# leo_joy_gamer.net
KiCad netlist of a schematic drawn in EAGLE
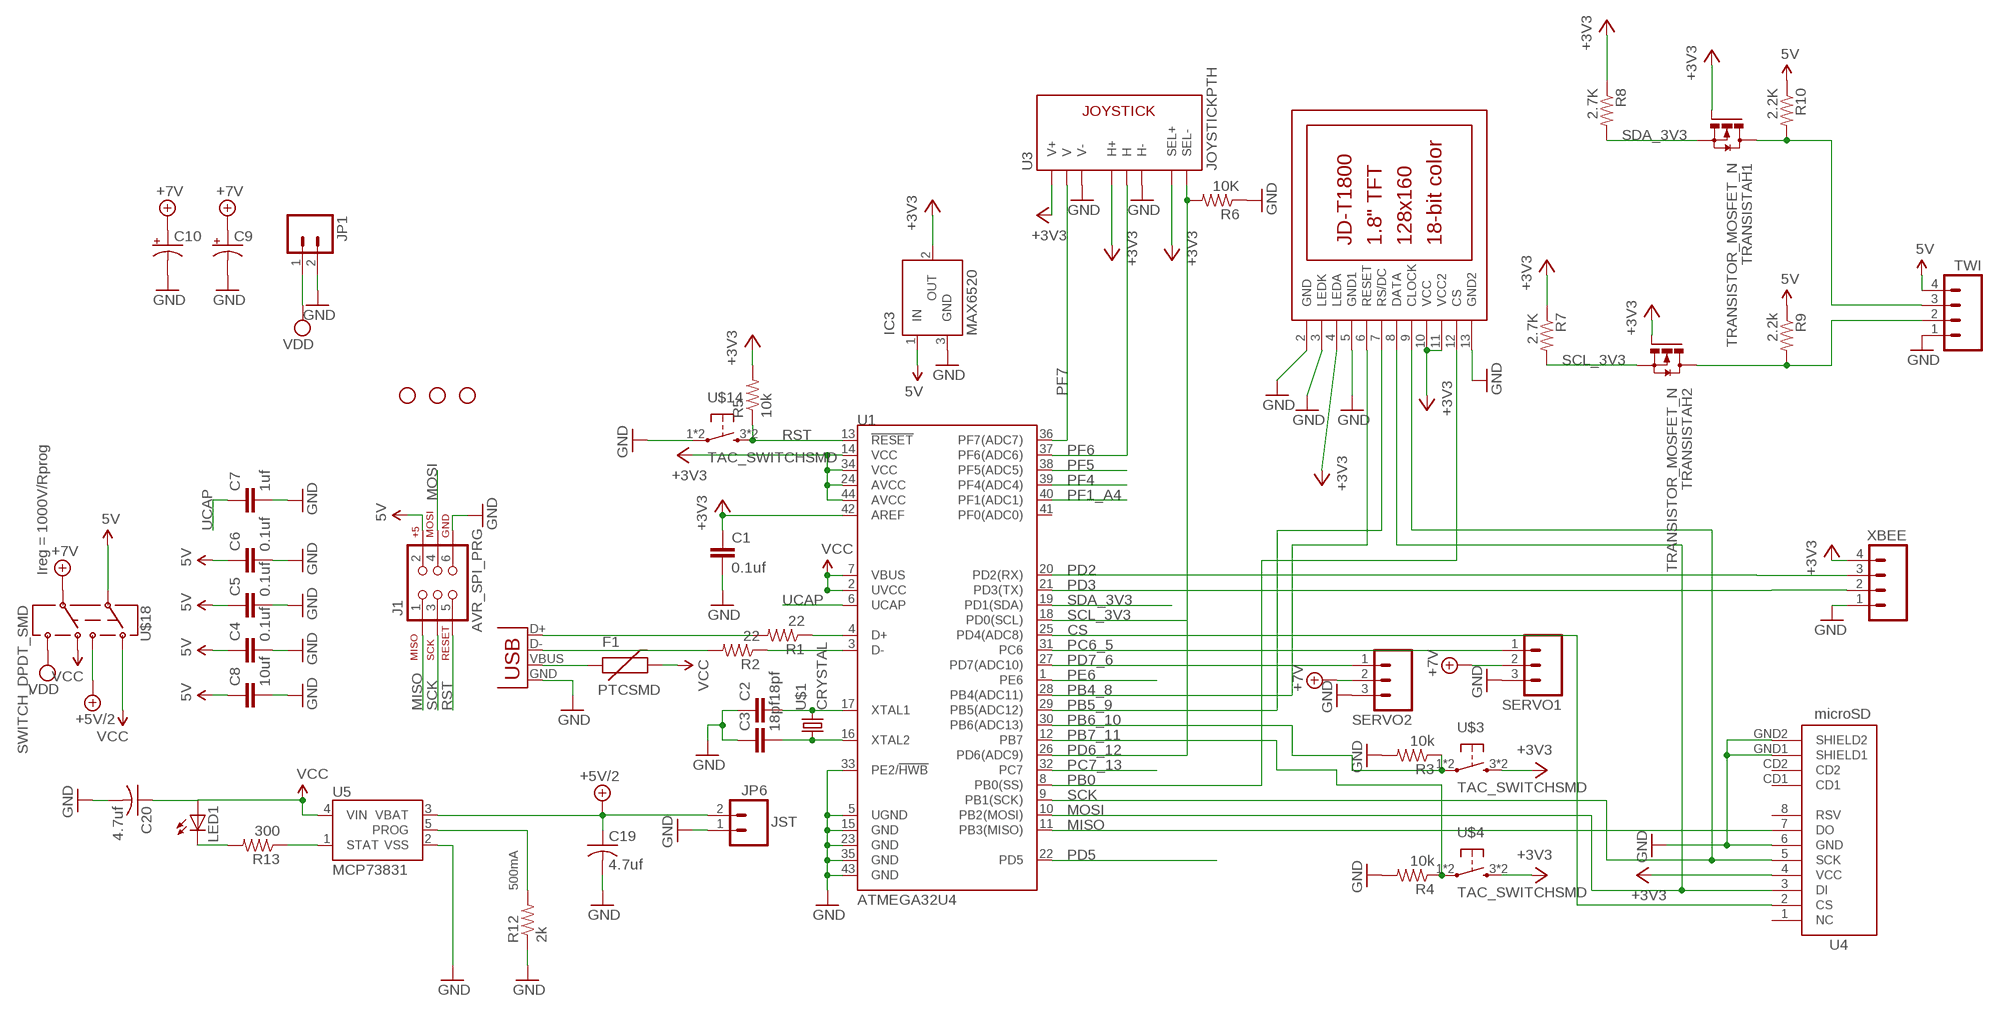
[diagram p0: schematic, sheet 1]

(export (version "E")
  (design (tool "Eeschema 10.0.6"))
  (components
    (comp (ref "C1")
      (value "0.1uf")
      (footprint "eagle-import:0805")
      (libsource (lib "eagle-import") (part "CAP0805"))
    )
    (comp (ref "C2")
      (value "18pf")
      (footprint "eagle-import:0805")
      (libsource (lib "eagle-import") (part "CAP0805"))
    )
    (comp (ref "C3")
      (value "18pf")
      (footprint "eagle-import:0805")
      (libsource (lib "eagle-import") (part "CAP0805"))
    )
    (comp (ref "C4")
      (value "0.1uf")
      (footprint "eagle-import:0805")
      (libsource (lib "eagle-import") (part "CAP0805"))
    )
    (comp (ref "C5")
      (value "0.1uf")
      (footprint "eagle-import:0805")
      (libsource (lib "eagle-import") (part "CAP0805"))
    )
    (comp (ref "C6")
      (value "0.1uf")
      (footprint "eagle-import:0805")
      (libsource (lib "eagle-import") (part "CAP0805"))
    )
    (comp (ref "C7")
      (value "1uf")
      (footprint "eagle-import:0805")
      (libsource (lib "eagle-import") (part "CAP0805"))
    )
    (comp (ref "C8")
      (value "10uf")
      (footprint "eagle-import:0805")
      (libsource (lib "eagle-import") (part "CAP0805"))
    )
    (comp (ref "C9")
      (value "CPOL-USD")
      (footprint "eagle-import:PANASONIC_D")
      (libsource (lib "eagle-import") (part "CPOL-USD"))
    )
    (comp (ref "C10")
      (value "CPOL-USD")
      (footprint "eagle-import:PANASONIC_D")
      (libsource (lib "eagle-import") (part "CPOL-USD"))
    )
    (comp (ref "C19")
      (value "4.7uf")
      (footprint "eagle-import:C0603")
      (libsource (lib "eagle-import") (part "C-USC0603"))
    )
    (comp (ref "C20")
      (value "4.7uf")
      (footprint "eagle-import:C0603")
      (libsource (lib "eagle-import") (part "C-USC0603"))
    )
    (comp (ref "F1")
      (value "PTCSMD")
      (footprint "eagle-import:PTC-1206")
      (libsource (lib "eagle-import") (part "PTCSMD"))
    )
    (comp (ref "IC3")
      (value "MAX6520")
      (footprint "eagle-import:SOT23")
      (libsource (lib "eagle-import") (part "MAX6520"))
    )
    (comp (ref "J1")
      (value "AVR_SPI_PRG")
      (footprint "eagle-import:2X3")
      (libsource (lib "eagle-import") (part "AVR_SPI_PRG_6PTH"))
    )
    (comp (ref "JP1")
      (value "M02LOCK")
      (footprint "eagle-import:1X02_LOCK")
      (libsource (lib "eagle-import") (part "M02LOCK"))
    )
    (comp (ref "JP2")
      (value "STAND-OFF")
      (footprint "eagle-import:STAND-OFF")
      (libsource (lib "eagle-import") (part "STAND-OFF"))
    )
    (comp (ref "JP3")
      (value "STAND-OFF")
      (footprint "eagle-import:STAND-OFF")
      (libsource (lib "eagle-import") (part "STAND-OFF"))
    )
    (comp (ref "JP4")
      (value "STAND-OFF")
      (footprint "eagle-import:STAND-OFF")
      (libsource (lib "eagle-import") (part "STAND-OFF"))
    )
    (comp (ref "JP6")
      (value "JST")
      (footprint "eagle-import:JST-2-PTH")
      (libsource (lib "eagle-import") (part "M02JST-PTH-2"))
    )
    (comp (ref "LCD1")
      (value "JD-T1800")
      (footprint "eagle-import:JD-T1800")
      (libsource (lib "eagle-import") (part "JD-T1800"))
    )
    (comp (ref "LED1")
      (value "LEDCHIPLED_1206")
      (footprint "eagle-import:CHIPLED_1206")
      (libsource (lib "eagle-import") (part "LEDCHIPLED_1206"))
    )
    (comp (ref "R1")
      (value "22")
      (footprint "eagle-import:M0805")
      (libsource (lib "eagle-import") (part "R-US_M0805"))
    )
    (comp (ref "R2")
      (value "22")
      (footprint "eagle-import:M0805")
      (libsource (lib "eagle-import") (part "R-US_M0805"))
    )
    (comp (ref "R3")
      (value "10k")
      (footprint "eagle-import:M0805")
      (libsource (lib "eagle-import") (part "R-US_M0805"))
    )
    (comp (ref "R4")
      (value "10k")
      (footprint "eagle-import:M0805")
      (libsource (lib "eagle-import") (part "R-US_M0805"))
    )
    (comp (ref "R5")
      (value "10k")
      (footprint "eagle-import:M0805")
      (libsource (lib "eagle-import") (part "R-US_M0805"))
    )
    (comp (ref "R6")
      (value "10K")
      (footprint "eagle-import:R0603")
      (libsource (lib "eagle-import") (part "R-US_R0603"))
    )
    (comp (ref "R7")
      (value "2.7K")
      (footprint "eagle-import:M0805")
      (libsource (lib "eagle-import") (part "R-US_M0805"))
    )
    (comp (ref "R8")
      (value "2.7K")
      (footprint "eagle-import:M0805")
      (libsource (lib "eagle-import") (part "R-US_M0805"))
    )
    (comp (ref "R9")
      (value "2.2k")
      (footprint "eagle-import:M0805")
      (libsource (lib "eagle-import") (part "R-US_M0805"))
    )
    (comp (ref "R10")
      (value "2.2K")
      (footprint "eagle-import:M0805")
      (libsource (lib "eagle-import") (part "R-US_M0805"))
    )
    (comp (ref "R12")
      (value "2k")
      (footprint "eagle-import:R0805")
      (libsource (lib "eagle-import") (part "R-US_R0805"))
    )
    (comp (ref "R13")
      (value "300")
      (footprint "eagle-import:R0805")
      (libsource (lib "eagle-import") (part "R-US_R0805"))
    )
    (comp (ref "SERVO1")
      (value "M03LOCK")
      (footprint "eagle-import:1X03_LOCK")
      (libsource (lib "eagle-import") (part "M03LOCK"))
    )
    (comp (ref "SERVO2")
      (value "M03LOCK")
      (footprint "eagle-import:1X03_LOCK")
      (libsource (lib "eagle-import") (part "M03LOCK"))
    )
    (comp (ref "TRANSISTAH1")
      (value "TRANSISTOR_MOSFET_N")
      (footprint "eagle-import:SOT23")
      (libsource (lib "eagle-import") (part "TRANSISTOR_MOSFET_N"))
    )
    (comp (ref "TRANSISTAH2")
      (value "TRANSISTOR_MOSFET_N")
      (footprint "eagle-import:SOT23")
      (libsource (lib "eagle-import") (part "TRANSISTOR_MOSFET_N"))
    )
    (comp (ref "TWI")
      (value "M04LOCK")
      (footprint "eagle-import:1X04_LOCK")
      (libsource (lib "eagle-import") (part "M04LOCK"))
    )
    (comp (ref "U$1")
      (value "CRYSTAL")
      (footprint "eagle-import:CRYSTAL_SMD")
      (libsource (lib "eagle-import") (part "CRYSTAL"))
    )
    (comp (ref "U$3")
      (value "TAC_SWITCHSMD")
      (footprint "eagle-import:TAC_SWITCH_SMD")
      (libsource (lib "eagle-import") (part "TAC_SWITCHSMD"))
    )
    (comp (ref "U$4")
      (value "TAC_SWITCHSMD")
      (footprint "eagle-import:TAC_SWITCH_SMD")
      (libsource (lib "eagle-import") (part "TAC_SWITCHSMD"))
    )
    (comp (ref "U$14")
      (value "TAC_SWITCHSMD")
      (footprint "eagle-import:TAC_SWITCH_SMD")
      (libsource (lib "eagle-import") (part "TAC_SWITCHSMD"))
    )
    (comp (ref "U$18")
      (value "SWITCH_DPDT_SMD")
      (footprint "eagle-import:SWITCH_DPDT")
      (libsource (lib "eagle-import") (part "SWITCH_DPDT_SMD"))
    )
    (comp (ref "U1")
      (value "ATMEGA32U4")
      (footprint "eagle-import:QFN-44-NOPAD")
      (libsource (lib "eagle-import") (part "ATMEGA32U4QFN2"))
    )
    (comp (ref "U3")
      (value "JOYSTICKPTH")
      (footprint "eagle-import:JOYSTICK")
      (libsource (lib "eagle-import") (part "JOYSTICKPTH"))
    )
    (comp (ref "U4")
      (value "microSD")
      (footprint "eagle-import:MICRO-SD-SOCKET-PP")
      (libsource (lib "eagle-import") (part "USD-SOCKETSMD"))
    )
    (comp (ref "U5")
      (value "MCP73831")
      (footprint "eagle-import:SOT23-5")
      (libsource (lib "eagle-import") (part "MCP73831"))
    )
    (comp (ref "X2")
      (value "USB-MICROB")
      (footprint "eagle-import:USB-MICROB")
      (libsource (lib "eagle-import") (part "USB-MICROB"))
    )
    (comp (ref "XBEE")
      (value "M04LOCK")
      (footprint "eagle-import:1X04_LOCK")
      (libsource (lib "eagle-import") (part "M04LOCK"))
    )
  )
  (nets
    (net (code "1") (name "+3V3") (class "Default")
      (node (ref "C1") (pin "1") (pinfunction "1_1") (pintype "passive"))
      (node (ref "IC3") (pin "2") (pinfunction "OUT_2") (pintype "input"))
      (node (ref "LCD1") (pin "10") (pinfunction "VCC_10") (pintype "power_in"))
      (node (ref "LCD1") (pin "11") (pinfunction "VCC2_11") (pintype "power_in"))
      (node (ref "LCD1") (pin "4") (pinfunction "LEDA_4") (pintype "input"))
      (node (ref "R5") (pin "2") (pinfunction "2_2") (pintype "passive"))
      (node (ref "R7") (pin "1") (pinfunction "1_1") (pintype "passive"))
      (node (ref "R8") (pin "1") (pinfunction "1_1") (pintype "passive"))
      (node (ref "TRANSISTAH1") (pin "1") (pinfunction "G_1") (pintype "passive"))
      (node (ref "TRANSISTAH2") (pin "1") (pinfunction "G_1") (pintype "passive"))
      (node (ref "U$3") (pin "3") (pinfunction "3_3") (pintype "passive"))
      (node (ref "U$3") (pin "4") (pinfunction "3_4") (pintype "passive"))
      (node (ref "U$4") (pin "3") (pinfunction "3_3") (pintype "passive"))
      (node (ref "U$4") (pin "4") (pinfunction "3_4") (pintype "passive"))
      (node (ref "U1") (pin "14") (pinfunction "VCC_14") (pintype "bidirectional"))
      (node (ref "U1") (pin "24") (pinfunction "AVCC_24") (pintype "bidirectional"))
      (node (ref "U1") (pin "34") (pinfunction "VCC_34") (pintype "bidirectional"))
      (node (ref "U1") (pin "42") (pinfunction "AREF_42") (pintype "bidirectional"))
      (node (ref "U1") (pin "44") (pinfunction "AVCC_44") (pintype "bidirectional"))
      (node (ref "U3") (pin "B1A") (pinfunction "SEL+_B1A") (pintype "bidirectional"))
      (node (ref "U3") (pin "H1") (pinfunction "H+_H1") (pintype "bidirectional"))
      (node (ref "U3") (pin "V1") (pinfunction "V+_V1") (pintype "bidirectional"))
      (node (ref "U4") (pin "4") (pinfunction "VCC_4") (pintype "bidirectional"))
      (node (ref "XBEE") (pin "4") (pinfunction "4_4") (pintype "passive"))
    )
    (net (code "2") (name "+5V{slash}2") (class "Default")
      (node (ref "C19") (pin "1") (pinfunction "1_1") (pintype "passive"))
      (node (ref "JP6") (pin "2") (pinfunction "2_2") (pintype "passive"))
      (node (ref "U$18") (pin "8") (pinfunction "3_8") (pintype "bidirectional"))
      (node (ref "U5") (pin "3") (pinfunction "VBAT_3") (pintype "power_in"))
    )
    (net (code "3") (name "+7V") (class "Default")
      (node (ref "C10") (pin "+") (pinfunction "+_+") (pintype "passive"))
      (node (ref "C9") (pin "+") (pinfunction "+_+") (pintype "passive"))
      (node (ref "SERVO1") (pin "2") (pinfunction "2_2") (pintype "passive"))
      (node (ref "SERVO2") (pin "2") (pinfunction "2_2") (pintype "passive"))
      (node (ref "U$18") (pin "10") (pinfunction "5_10") (pintype "bidirectional"))
    )
    (net (code "4") (name "/CS") (class "Default")
      (node (ref "U1") (pin "25") (pinfunction "PD4(ADC8)_25") (pintype "bidirectional"))
      (node (ref "U4") (pin "2") (pinfunction "CS_2") (pintype "bidirectional"))
    )
    (net (code "5") (name "/MISO") (class "Default")
      (node (ref "J1") (pin "1") (pinfunction "1_1") (pintype "passive"))
      (node (ref "U1") (pin "11") (pinfunction "PB3(MISO)_11") (pintype "bidirectional"))
      (node (ref "U4") (pin "7") (pinfunction "DO_7") (pintype "bidirectional"))
    )
    (net (code "6") (name "/MOSI") (class "Default")
      (node (ref "J1") (pin "4") (pinfunction "4_4") (pintype "passive"))
      (node (ref "LCD1") (pin "8") (pinfunction "DATA_8") (pintype "bidirectional"))
      (node (ref "U1") (pin "10") (pinfunction "PB2(MOSI)_10") (pintype "bidirectional"))
      (node (ref "U4") (pin "3") (pinfunction "DI_3") (pintype "bidirectional"))
    )
    (net (code "7") (name "/PB0") (class "Default")
      (node (ref "LCD1") (pin "12") (pinfunction "CS_12") (pintype "input"))
      (node (ref "U1") (pin "8") (pinfunction "PB0(SS)_8") (pintype "bidirectional"))
    )
    (net (code "8") (name "/PB4_8") (class "Default")
      (node (ref "LCD1") (pin "6") (pinfunction "RESET_6") (pintype "input"))
      (node (ref "U1") (pin "28") (pinfunction "PB4(ADC11)_28") (pintype "bidirectional"))
    )
    (net (code "9") (name "/PB5_9") (class "Default")
      (node (ref "LCD1") (pin "7") (pinfunction "RS/DC_7") (pintype "input"))
      (node (ref "U1") (pin "29") (pinfunction "PB5(ADC12)_29") (pintype "bidirectional"))
    )
    (net (code "10") (name "/PB6_10") (class "Default")
      (node (ref "R3") (pin "1") (pinfunction "1_1") (pintype "passive"))
      (node (ref "U$3") (pin "1") (pinfunction "1_1") (pintype "passive"))
      (node (ref "U$3") (pin "2") (pinfunction "1_2") (pintype "passive"))
      (node (ref "U1") (pin "30") (pinfunction "PB6(ADC13)_30") (pintype "bidirectional"))
    )
    (net (code "11") (name "/PB7_11") (class "Default")
      (node (ref "R4") (pin "1") (pinfunction "1_1") (pintype "passive"))
      (node (ref "U$4") (pin "1") (pinfunction "1_1") (pintype "passive"))
      (node (ref "U$4") (pin "2") (pinfunction "1_2") (pintype "passive"))
      (node (ref "U1") (pin "12") (pinfunction "PB7_12") (pintype "bidirectional"))
    )
    (net (code "12") (name "/PC6_5") (class "Default")
      (node (ref "SERVO1") (pin "1") (pinfunction "1_1") (pintype "passive"))
      (node (ref "U1") (pin "31") (pinfunction "PC6_31") (pintype "bidirectional"))
    )
    (net (code "13") (name "/PC7_13") (class "Default")
      (node (ref "U1") (pin "32") (pinfunction "PC7_32") (pintype "bidirectional"))
    )
    (net (code "14") (name "/PD2") (class "Default")
      (node (ref "U1") (pin "20") (pinfunction "PD2(RX)_20") (pintype "bidirectional"))
      (node (ref "XBEE") (pin "3") (pinfunction "3_3") (pintype "passive"))
    )
    (net (code "15") (name "/PD3") (class "Default")
      (node (ref "U1") (pin "21") (pinfunction "PD3(TX)_21") (pintype "bidirectional"))
      (node (ref "XBEE") (pin "2") (pinfunction "2_2") (pintype "passive"))
    )
    (net (code "16") (name "/PD5") (class "Default")
      (node (ref "U1") (pin "22") (pinfunction "PD5_22") (pintype "bidirectional"))
    )
    (net (code "17") (name "/PD6_12") (class "Default")
      (node (ref "R6") (pin "2") (pinfunction "2_2") (pintype "passive"))
      (node (ref "U1") (pin "26") (pinfunction "PD6(ADC9)_26") (pintype "bidirectional"))
      (node (ref "U3") (pin "B2A") (pinfunction "SEL-_B2A") (pintype "bidirectional"))
    )
    (net (code "18") (name "/PD7_6") (class "Default")
      (node (ref "SERVO2") (pin "1") (pinfunction "1_1") (pintype "passive"))
      (node (ref "U1") (pin "27") (pinfunction "PD7(ADC10)_27") (pintype "bidirectional"))
    )
    (net (code "19") (name "/PE6") (class "Default")
      (node (ref "U1") (pin "1") (pinfunction "PE6_1") (pintype "bidirectional"))
    )
    (net (code "20") (name "/PF1_A4") (class "Default")
      (node (ref "U1") (pin "40") (pinfunction "PF1(ADC1)_40") (pintype "bidirectional"))
    )
    (net (code "21") (name "/PF4") (class "Default")
      (node (ref "U1") (pin "39") (pinfunction "PF4(ADC4)_39") (pintype "bidirectional"))
    )
    (net (code "22") (name "/PF5") (class "Default")
      (node (ref "U1") (pin "38") (pinfunction "PF5(ADC5)_38") (pintype "bidirectional"))
    )
    (net (code "23") (name "/PF6") (class "Default")
      (node (ref "U1") (pin "37") (pinfunction "PF6(ADC6)_37") (pintype "bidirectional"))
      (node (ref "U3") (pin "H2") (pinfunction "H_H2") (pintype "bidirectional"))
    )
    (net (code "24") (name "/PF7") (class "Default")
      (node (ref "U1") (pin "36") (pinfunction "PF7(ADC7)_36") (pintype "bidirectional"))
      (node (ref "U3") (pin "V2") (pinfunction "V_V2") (pintype "bidirectional"))
    )
    (net (code "25") (name "/RST") (class "Default")
      (node (ref "J1") (pin "5") (pinfunction "5_5") (pintype "passive"))
      (node (ref "R5") (pin "1") (pinfunction "1_1") (pintype "passive"))
      (node (ref "U$14") (pin "3") (pinfunction "3_3") (pintype "passive"))
      (node (ref "U$14") (pin "4") (pinfunction "3_4") (pintype "passive"))
      (node (ref "U1") (pin "13") (pinfunction "~{RESET}_13") (pintype "bidirectional"))
    )
    (net (code "26") (name "/SCK") (class "Default")
      (node (ref "J1") (pin "3") (pinfunction "3_3") (pintype "passive"))
      (node (ref "LCD1") (pin "9") (pinfunction "CLOCK_9") (pintype "input"))
      (node (ref "U1") (pin "9") (pinfunction "PB1(SCK)_9") (pintype "bidirectional"))
      (node (ref "U4") (pin "5") (pinfunction "SCK_5") (pintype "bidirectional"))
    )
    (net (code "27") (name "/SCL_3V3") (class "Default")
      (node (ref "R7") (pin "2") (pinfunction "2_2") (pintype "passive"))
      (node (ref "TRANSISTAH2") (pin "2") (pinfunction "S_2") (pintype "passive"))
      (node (ref "U1") (pin "18") (pinfunction "PD0(SCL)_18") (pintype "bidirectional"))
    )
    (net (code "28") (name "/SDA_3V3") (class "Default")
      (node (ref "R8") (pin "2") (pinfunction "2_2") (pintype "passive"))
      (node (ref "TRANSISTAH1") (pin "2") (pinfunction "S_2") (pintype "passive"))
      (node (ref "U1") (pin "19") (pinfunction "PD1(SDA)_19") (pintype "bidirectional"))
    )
    (net (code "29") (name "/UCAP") (class "Default")
      (node (ref "C7") (pin "1") (pinfunction "1_1") (pintype "passive"))
      (node (ref "U1") (pin "6") (pinfunction "UCAP_6") (pintype "bidirectional"))
    )
    (net (code "30") (name "5V") (class "Default")
      (node (ref "C4") (pin "1") (pinfunction "1_1") (pintype "passive"))
      (node (ref "C5") (pin "1") (pinfunction "1_1") (pintype "passive"))
      (node (ref "C6") (pin "1") (pinfunction "1_1") (pintype "passive"))
      (node (ref "C8") (pin "1") (pinfunction "1_1") (pintype "passive"))
      (node (ref "IC3") (pin "1") (pinfunction "IN_1") (pintype "input"))
      (node (ref "J1") (pin "2") (pinfunction "2_2") (pintype "passive"))
      (node (ref "R10") (pin "1") (pinfunction "1_1") (pintype "passive"))
      (node (ref "R9") (pin "1") (pinfunction "1_1") (pintype "passive"))
      (node (ref "TWI") (pin "4") (pinfunction "4_4") (pintype "passive"))
      (node (ref "U$18") (pin "7") (pinfunction "2_7") (pintype "bidirectional"))
    )
    (net (code "31") (name "GND") (class "Default")
      (node (ref "C1") (pin "2") (pinfunction "2_2") (pintype "passive"))
      (node (ref "C10") (pin "-") (pinfunction "-_-") (pintype "passive"))
      (node (ref "C19") (pin "2") (pinfunction "2_2") (pintype "passive"))
      (node (ref "C2") (pin "1") (pinfunction "1_1") (pintype "passive"))
      (node (ref "C20") (pin "2") (pinfunction "2_2") (pintype "passive"))
      (node (ref "C3") (pin "1") (pinfunction "1_1") (pintype "passive"))
      (node (ref "C4") (pin "2") (pinfunction "2_2") (pintype "passive"))
      (node (ref "C5") (pin "2") (pinfunction "2_2") (pintype "passive"))
      (node (ref "C6") (pin "2") (pinfunction "2_2") (pintype "passive"))
      (node (ref "C7") (pin "2") (pinfunction "2_2") (pintype "passive"))
      (node (ref "C8") (pin "2") (pinfunction "2_2") (pintype "passive"))
      (node (ref "C9") (pin "-") (pinfunction "-_-") (pintype "passive"))
      (node (ref "IC3") (pin "3") (pinfunction "GND_3") (pintype "power_in"))
      (node (ref "J1") (pin "6") (pinfunction "6_6") (pintype "passive"))
      (node (ref "JP1") (pin "2") (pinfunction "2_2") (pintype "passive"))
      (node (ref "JP6") (pin "1") (pinfunction "1_1") (pintype "passive"))
      (node (ref "LCD1") (pin "13") (pinfunction "GND2_13") (pintype "power_in"))
      (node (ref "LCD1") (pin "2") (pinfunction "GND_2") (pintype "power_in"))
      (node (ref "LCD1") (pin "3") (pinfunction "LEDK_3") (pintype "input"))
      (node (ref "LCD1") (pin "5") (pinfunction "GND1_5") (pintype "power_in"))
      (node (ref "R12") (pin "1") (pinfunction "1_1") (pintype "passive"))
      (node (ref "R3") (pin "2") (pinfunction "2_2") (pintype "passive"))
      (node (ref "R4") (pin "2") (pinfunction "2_2") (pintype "passive"))
      (node (ref "R6") (pin "1") (pinfunction "1_1") (pintype "passive"))
      (node (ref "SERVO1") (pin "3") (pinfunction "3_3") (pintype "passive"))
      (node (ref "SERVO2") (pin "3") (pinfunction "3_3") (pintype "passive"))
      (node (ref "TWI") (pin "1") (pinfunction "1_1") (pintype "passive"))
      (node (ref "U$14") (pin "1") (pinfunction "1_1") (pintype "passive"))
      (node (ref "U$14") (pin "2") (pinfunction "1_2") (pintype "passive"))
      (node (ref "U1") (pin "15") (pinfunction "GND_15") (pintype "bidirectional"))
      (node (ref "U1") (pin "23") (pinfunction "GND_23") (pintype "bidirectional"))
      (node (ref "U1") (pin "33") (pinfunction "PE2/~{HWB}_33") (pintype "bidirectional"))
      (node (ref "U1") (pin "35") (pinfunction "GND_35") (pintype "bidirectional"))
      (node (ref "U1") (pin "43") (pinfunction "GND_43") (pintype "bidirectional"))
      (node (ref "U1") (pin "5") (pinfunction "UGND_5") (pintype "bidirectional"))
      (node (ref "U3") (pin "H3") (pinfunction "H-_H3") (pintype "bidirectional"))
      (node (ref "U3") (pin "V3") (pinfunction "V-_V3") (pintype "bidirectional"))
      (node (ref "U4") (pin "6") (pinfunction "GND_6") (pintype "bidirectional"))
      (node (ref "U4") (pin "GND1") (pinfunction "SHIELD1_GND1") (pintype "bidirectional"))
      (node (ref "U4") (pin "GND2") (pinfunction "SHIELD2_GND2") (pintype "bidirectional"))
      (node (ref "U5") (pin "2") (pinfunction "VSS_2") (pintype "power_in"))
      (node (ref "X2") (pin "GND") (pinfunction "GND_GND") (pintype "bidirectional"))
      (node (ref "XBEE") (pin "1") (pinfunction "1_1") (pintype "passive"))
    )
    (net (code "32") (name "Net-(F1-Pad1)") (class "Default")
      (node (ref "F1") (pin "1") (pinfunction "1_1") (pintype "bidirectional"))
      (node (ref "X2") (pin "VBUS") (pinfunction "VBUS_VBUS") (pintype "bidirectional"))
    )
    (net (code "33") (name "Net-(LED1-PadC)") (class "Default")
      (node (ref "LED1") (pin "C") (pinfunction "C_C") (pintype "passive"))
      (node (ref "R13") (pin "2") (pinfunction "2_2") (pintype "passive"))
    )
    (net (code "34") (name "Net-(R1-Pad2)") (class "Default")
      (node (ref "R1") (pin "2") (pinfunction "2_2") (pintype "passive"))
      (node (ref "X2") (pin "D+") (pinfunction "D+_D+") (pintype "bidirectional"))
    )
    (net (code "35") (name "Net-(R2-Pad2)") (class "Default")
      (node (ref "R2") (pin "2") (pinfunction "2_2") (pintype "passive"))
      (node (ref "X2") (pin "D-") (pinfunction "D-_D-") (pintype "bidirectional"))
    )
    (net (code "36") (name "Net-(TRANSISTAH1-D)") (class "Default")
      (node (ref "R10") (pin "2") (pinfunction "2_2") (pintype "passive"))
      (node (ref "TRANSISTAH1") (pin "3") (pinfunction "D_3") (pintype "passive"))
      (node (ref "TWI") (pin "3") (pinfunction "3_3") (pintype "passive"))
    )
    (net (code "37") (name "Net-(TRANSISTAH2-D)") (class "Default")
      (node (ref "R9") (pin "2") (pinfunction "2_2") (pintype "passive"))
      (node (ref "TRANSISTAH2") (pin "3") (pinfunction "D_3") (pintype "passive"))
      (node (ref "TWI") (pin "2") (pinfunction "2_2") (pintype "passive"))
    )
    (net (code "38") (name "Net-(U1-D+)") (class "Default")
      (node (ref "R1") (pin "1") (pinfunction "1_1") (pintype "passive"))
      (node (ref "U1") (pin "4") (pinfunction "D+_4") (pintype "bidirectional"))
    )
    (net (code "39") (name "Net-(U1-D-)") (class "Default")
      (node (ref "R2") (pin "1") (pinfunction "1_1") (pintype "passive"))
      (node (ref "U1") (pin "3") (pinfunction "D-_3") (pintype "bidirectional"))
    )
    (net (code "40") (name "Net-(U1-XTAL1)") (class "Default")
      (node (ref "C2") (pin "2") (pinfunction "2_2") (pintype "passive"))
      (node (ref "U$1") (pin "2") (pinfunction "2_2") (pintype "passive"))
      (node (ref "U1") (pin "17") (pinfunction "XTAL1_17") (pintype "bidirectional"))
    )
    (net (code "41") (name "Net-(U1-XTAL2)") (class "Default")
      (node (ref "C3") (pin "2") (pinfunction "2_2") (pintype "passive"))
      (node (ref "U$1") (pin "1") (pinfunction "1_1") (pintype "passive"))
      (node (ref "U1") (pin "16") (pinfunction "XTAL2_16") (pintype "bidirectional"))
    )
    (net (code "42") (name "Net-(U5-PROG)") (class "Default")
      (node (ref "R12") (pin "2") (pinfunction "2_2") (pintype "passive"))
      (node (ref "U5") (pin "5") (pinfunction "PROG_5") (pintype "input"))
    )
    (net (code "43") (name "Net-(U5-STAT)") (class "Default")
      (node (ref "R13") (pin "1") (pinfunction "1_1") (pintype "passive"))
      (node (ref "U5") (pin "1") (pinfunction "STAT_1") (pintype "output"))
    )
    (net (code "44") (name "VCC") (class "Default")
      (node (ref "C20") (pin "1") (pinfunction "1_1") (pintype "passive"))
      (node (ref "F1") (pin "2") (pinfunction "2_2") (pintype "bidirectional"))
      (node (ref "LED1") (pin "A") (pinfunction "A_A") (pintype "passive"))
      (node (ref "U$18") (pin "1") (pinfunction "1_1") (pintype "bidirectional"))
      (node (ref "U$18") (pin "9") (pinfunction "4_9") (pintype "bidirectional"))
      (node (ref "U1") (pin "2") (pinfunction "UVCC_2") (pintype "bidirectional"))
      (node (ref "U1") (pin "7") (pinfunction "VBUS_7") (pintype "bidirectional"))
      (node (ref "U5") (pin "4") (pinfunction "VIN_4") (pintype "power_in"))
    )
    (net (code "45") (name "VDD") (class "Default")
      (node (ref "JP1") (pin "1") (pinfunction "1_1") (pintype "passive"))
      (node (ref "U$18") (pin "11") (pinfunction "6_11") (pintype "bidirectional"))
    )
    (net (code "46") (name "unconnected-(U1-PF0(ADC0)-Pad41)") (class "Default")
      (node (ref "U1") (pin "41") (pinfunction "PF0(ADC0)_41") (pintype "bidirectional"))
    )
    (net (code "47") (name "unconnected-(U4-NC-Pad1)") (class "Default")
      (node (ref "U4") (pin "1") (pinfunction "NC_1") (pintype "bidirectional"))
    )
    (net (code "48") (name "unconnected-(U4-PadCD1)") (class "Default")
      (node (ref "U4") (pin "CD1") (pinfunction "CD1_CD1") (pintype "bidirectional"))
    )
    (net (code "49") (name "unconnected-(U4-PadCD2)") (class "Default")
      (node (ref "U4") (pin "CD2") (pinfunction "CD2_CD2") (pintype "bidirectional"))
    )
    (net (code "50") (name "unconnected-(U4-RSV-Pad8)") (class "Default")
      (node (ref "U4") (pin "8") (pinfunction "RSV_8") (pintype "bidirectional"))
    )
  )
)
